# ReactanciaCapacitiva.net
KiCad netlist of a schematic drawn in EAGLE
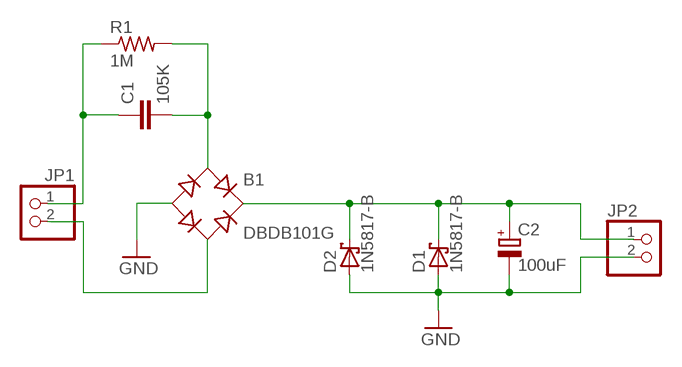
[diagram p0: schematic, sheet 1]

(export (version "E")
  (design (tool "Eeschema 10.0.6"))
  (components
    (comp (ref "B1")
      (value "DBDB101G")
      (footprint "eagle-import:DB")
      (libsource (lib "eagle-import") (part "DB?GDB101"))
    )
    (comp (ref "C1")
      (value "105K")
      (footprint "eagle-import:C15B7")
      (libsource (lib "eagle-import") (part "C15/7"))
    )
    (comp (ref "C2")
      (value "100uF")
      (footprint "eagle-import:E2,5-7")
      (libsource (lib "eagle-import") (part "CPOL-EUE2.5-7"))
    )
    (comp (ref "D1")
      (value "1N5817-B")
      (footprint "eagle-import:DO41-7.6")
      (libsource (lib "eagle-import") (part "1N5817-B"))
    )
    (comp (ref "D2")
      (value "1N5817-B")
      (footprint "eagle-import:DO41-7.6")
      (libsource (lib "eagle-import") (part "1N5817-B"))
    )
    (comp (ref "JP1")
      (value "PINHD-1X2/90")
      (footprint "eagle-import:1X02_90")
      (libsource (lib "eagle-import") (part "PINHD-1X2/90"))
    )
    (comp (ref "JP2")
      (value "PINHD-1X2")
      (footprint "eagle-import:1X02")
      (libsource (lib "eagle-import") (part "PINHD-1X2"))
    )
    (comp (ref "R1")
      (value "1M")
      (footprint "eagle-import:0204_7")
      (libsource (lib "eagle-import") (part "R-US_0204/7"))
    )
  )
  (nets
    (net (code "1") (name "GND") (class "Default")
      (node (ref "B1") (pin "-") (pinfunction "-_-") (pintype "passive"))
      (node (ref "C2") (pin "-") (pinfunction "-_-") (pintype "passive"))
      (node (ref "D1") (pin "A") (pinfunction "A_A") (pintype "passive"))
      (node (ref "D2") (pin "A") (pinfunction "A_A") (pintype "passive"))
      (node (ref "JP2") (pin "2") (pinfunction "2_2") (pintype "passive"))
    )
    (net (code "2") (name "Net-(B1-Pad+)") (class "Default")
      (node (ref "B1") (pin "+") (pinfunction "+_+") (pintype "passive"))
      (node (ref "C2") (pin "+") (pinfunction "+_+") (pintype "passive"))
      (node (ref "D1") (pin "C") (pinfunction "C_C") (pintype "passive"))
      (node (ref "D2") (pin "C") (pinfunction "C_C") (pintype "passive"))
      (node (ref "JP2") (pin "1") (pinfunction "1_1") (pintype "passive"))
    )
    (net (code "3") (name "Net-(B1-PadAC1)") (class "Default")
      (node (ref "B1") (pin "AC1") (pinfunction "AC1_AC1") (pintype "passive"))
      (node (ref "C1") (pin "2") (pinfunction "2_2") (pintype "passive"))
      (node (ref "R1") (pin "2") (pinfunction "2_2") (pintype "passive"))
    )
    (net (code "4") (name "Net-(B1-PadAC2)") (class "Default")
      (node (ref "B1") (pin "AC2") (pinfunction "AC2_AC2") (pintype "passive"))
      (node (ref "JP1") (pin "2") (pinfunction "2_2") (pintype "passive"))
    )
    (net (code "5") (name "Net-(C1-Pad1)") (class "Default")
      (node (ref "C1") (pin "1") (pinfunction "1_1") (pintype "passive"))
      (node (ref "JP1") (pin "1") (pinfunction "1_1") (pintype "passive"))
      (node (ref "R1") (pin "1") (pinfunction "1_1") (pintype "passive"))
    )
  )
)
